# Controller.net
KiCad netlist of a schematic drawn in Altium Designer
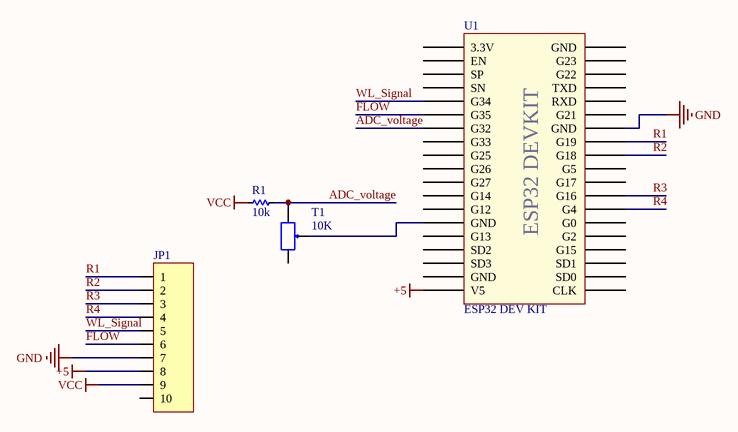
[diagram p0: Controller.SchDoc]

(export (version "E")
  (design (tool "Eeschema 10.0.6"))
  (components
    (comp (ref "JP1")
      (value "JP 1x10 2.54")
      (footprint "JP 1x10 DC")
      (description "Cắm")
      (libsource (lib "Altium_Lib_by_KhueNguyenCreator") (part "JP 1x10 2.54 Duc Cong"))
    )
    (comp (ref "R1")
      (value "10k")
      (footprint "RES-1/4W")
      (description "Res")
      (fields
        (field (name "MANUFACTURER") "Generic Components")
        (field (name "PUBLISHER") "Altium Hobart Technology Centre")
      )
      (libsource (lib "LIBRARY1") (part "Res"))
    )
    (comp (ref "T1")
      (value "10K")
      (footprint "BIEN TRO VI CHINH NAM")
      (description "Cắm")
      (libsource (lib "Altium_Lib_by_KhueNguyenCreator") (part "Bien Tro Tinh Chinh 10K Nam"))
    )
    (comp (ref "U1")
      (value "ESP32 DEV KIT")
      (footprint "ESP32 DEVKIT")
      (libsource (lib "Altium_Lib_by_KhueNguyenCreator") (part "ESP32 DEV KIT"))
    )
  )
  (nets
    (net (code "1") (name "+5") (class "Default")
      (node (ref "JP1") (pin "8") (pinfunction "8_8") (pintype "passive"))
      (node (ref "U1") (pin "19") (pinfunction "V5_19") (pintype "passive"))
    )
    (net (code "2") (name "/ADC_voltage") (class "Default")
      (node (ref "R1") (pin "1") (pinfunction "1_1") (pintype "passive"))
      (node (ref "T1") (pin "1") (pinfunction "1_1") (pintype "passive"))
      (node (ref "U1") (pin "7") (pinfunction "G32_7") (pintype "passive"))
    )
    (net (code "3") (name "/FLOW") (class "Default")
      (node (ref "JP1") (pin "6") (pinfunction "6_6") (pintype "passive"))
      (node (ref "U1") (pin "6") (pinfunction "G35_6") (pintype "passive"))
    )
    (net (code "4") (name "/R1") (class "Default")
      (node (ref "JP1") (pin "1") (pinfunction "1_1") (pintype "passive"))
      (node (ref "U1") (pin "31") (pinfunction "G19_31") (pintype "passive"))
    )
    (net (code "5") (name "/R2") (class "Default")
      (node (ref "JP1") (pin "2") (pinfunction "2_2") (pintype "passive"))
      (node (ref "U1") (pin "30") (pinfunction "G18_30") (pintype "passive"))
    )
    (net (code "6") (name "/R3") (class "Default")
      (node (ref "JP1") (pin "3") (pinfunction "3_3") (pintype "passive"))
      (node (ref "U1") (pin "27") (pinfunction "G16_27") (pintype "passive"))
    )
    (net (code "7") (name "/R4") (class "Default")
      (node (ref "JP1") (pin "4") (pinfunction "4_4") (pintype "passive"))
      (node (ref "U1") (pin "26") (pinfunction "G4_26") (pintype "passive"))
    )
    (net (code "8") (name "/WL_Signal") (class "Default")
      (node (ref "JP1") (pin "5") (pinfunction "5_5") (pintype "passive"))
      (node (ref "U1") (pin "5") (pinfunction "G34_5") (pintype "passive"))
    )
    (net (code "9") (name "GND") (class "Default")
      (node (ref "JP1") (pin "7") (pinfunction "7_7") (pintype "passive"))
      (node (ref "U1") (pin "32") (pinfunction "GND_32") (pintype "passive"))
    )
    (net (code "10") (name "Net-(T1-Pad2)") (class "Default")
      (node (ref "T1") (pin "2") (pinfunction "2_2") (pintype "passive"))
      (node (ref "U1") (pin "14") (pinfunction "GND_14") (pintype "passive"))
    )
    (net (code "11") (name "VCC") (class "Default")
      (node (ref "JP1") (pin "9") (pinfunction "9_9") (pintype "passive"))
      (node (ref "R1") (pin "2") (pinfunction "2_2") (pintype "passive"))
    )
    (net (code "12") (name "unconnected-(JP1-Pad10)") (class "Default")
      (node (ref "JP1") (pin "10") (pinfunction "10_10") (pintype "passive"))
    )
    (net (code "13") (name "unconnected-(T1-Pad3)") (class "Default")
      (node (ref "T1") (pin "3") (pinfunction "3_3") (pintype "passive"))
    )
    (net (code "14") (name "unconnected-(U1-3.3V-Pad1)") (class "Default")
      (node (ref "U1") (pin "1") (pinfunction "3.3V_1") (pintype "passive"))
    )
    (net (code "15") (name "unconnected-(U1-CLK-Pad20)") (class "Default")
      (node (ref "U1") (pin "20") (pinfunction "CLK_20") (pintype "passive"))
    )
    (net (code "16") (name "unconnected-(U1-EN-Pad2)") (class "Default")
      (node (ref "U1") (pin "2") (pinfunction "EN_2") (pintype "passive"))
    )
    (net (code "17") (name "unconnected-(U1-G0-Pad25)") (class "Default")
      (node (ref "U1") (pin "25") (pinfunction "G0_25") (pintype "passive"))
    )
    (net (code "18") (name "unconnected-(U1-G2-Pad24)") (class "Default")
      (node (ref "U1") (pin "24") (pinfunction "G2_24") (pintype "passive"))
    )
    (net (code "19") (name "unconnected-(U1-G5-Pad29)") (class "Default")
      (node (ref "U1") (pin "29") (pinfunction "G5_29") (pintype "passive"))
    )
    (net (code "20") (name "unconnected-(U1-G12-Pad13)") (class "Default")
      (node (ref "U1") (pin "13") (pinfunction "G12_13") (pintype "passive"))
    )
    (net (code "21") (name "unconnected-(U1-G13-Pad15)") (class "Default")
      (node (ref "U1") (pin "15") (pinfunction "G13_15") (pintype "passive"))
    )
    (net (code "22") (name "unconnected-(U1-G14-Pad12)") (class "Default")
      (node (ref "U1") (pin "12") (pinfunction "G14_12") (pintype "passive"))
    )
    (net (code "23") (name "unconnected-(U1-G15-Pad23)") (class "Default")
      (node (ref "U1") (pin "23") (pinfunction "G15_23") (pintype "passive"))
    )
    (net (code "24") (name "unconnected-(U1-G17-Pad28)") (class "Default")
      (node (ref "U1") (pin "28") (pinfunction "G17_28") (pintype "passive"))
    )
    (net (code "25") (name "unconnected-(U1-G21-Pad33)") (class "Default")
      (node (ref "U1") (pin "33") (pinfunction "G21_33") (pintype "passive"))
    )
    (net (code "26") (name "unconnected-(U1-G22-Pad36)") (class "Default")
      (node (ref "U1") (pin "36") (pinfunction "G22_36") (pintype "passive"))
    )
    (net (code "27") (name "unconnected-(U1-G23-Pad37)") (class "Default")
      (node (ref "U1") (pin "37") (pinfunction "G23_37") (pintype "passive"))
    )
    (net (code "28") (name "unconnected-(U1-G25-Pad9)") (class "Default")
      (node (ref "U1") (pin "9") (pinfunction "G25_9") (pintype "passive"))
    )
    (net (code "29") (name "unconnected-(U1-G26-Pad10)") (class "Default")
      (node (ref "U1") (pin "10") (pinfunction "G26_10") (pintype "passive"))
    )
    (net (code "30") (name "unconnected-(U1-G27-Pad11)") (class "Default")
      (node (ref "U1") (pin "11") (pinfunction "G27_11") (pintype "passive"))
    )
    (net (code "31") (name "unconnected-(U1-G33-Pad8)") (class "Default")
      (node (ref "U1") (pin "8") (pinfunction "G33_8") (pintype "passive"))
    )
    (net (code "32") (name "unconnected-(U1-GND-Pad18)") (class "Default")
      (node (ref "U1") (pin "18") (pinfunction "GND_18") (pintype "passive"))
    )
    (net (code "33") (name "unconnected-(U1-GND-Pad38)") (class "Default")
      (node (ref "U1") (pin "38") (pinfunction "GND_38") (pintype "passive"))
    )
    (net (code "34") (name "unconnected-(U1-RXD-Pad34)") (class "Default")
      (node (ref "U1") (pin "34") (pinfunction "RXD_34") (pintype "passive"))
    )
    (net (code "35") (name "unconnected-(U1-SD0-Pad21)") (class "Default")
      (node (ref "U1") (pin "21") (pinfunction "SD0_21") (pintype "passive"))
    )
    (net (code "36") (name "unconnected-(U1-SD1-Pad22)") (class "Default")
      (node (ref "U1") (pin "22") (pinfunction "SD1_22") (pintype "passive"))
    )
    (net (code "37") (name "unconnected-(U1-SD2-Pad16)") (class "Default")
      (node (ref "U1") (pin "16") (pinfunction "SD2_16") (pintype "passive"))
    )
    (net (code "38") (name "unconnected-(U1-SD3-Pad17)") (class "Default")
      (node (ref "U1") (pin "17") (pinfunction "SD3_17") (pintype "passive"))
    )
    (net (code "39") (name "unconnected-(U1-SN-Pad4)") (class "Default")
      (node (ref "U1") (pin "4") (pinfunction "SN_4") (pintype "passive"))
    )
    (net (code "40") (name "unconnected-(U1-SP-Pad3)") (class "Default")
      (node (ref "U1") (pin "3") (pinfunction "SP_3") (pintype "passive"))
    )
    (net (code "41") (name "unconnected-(U1-TXD-Pad35)") (class "Default")
      (node (ref "U1") (pin "35") (pinfunction "TXD_35") (pintype "passive"))
    )
  )
)
